# Carte_Servo_Robot_2.net
KiCad netlist of a schematic drawn in Altium Designer
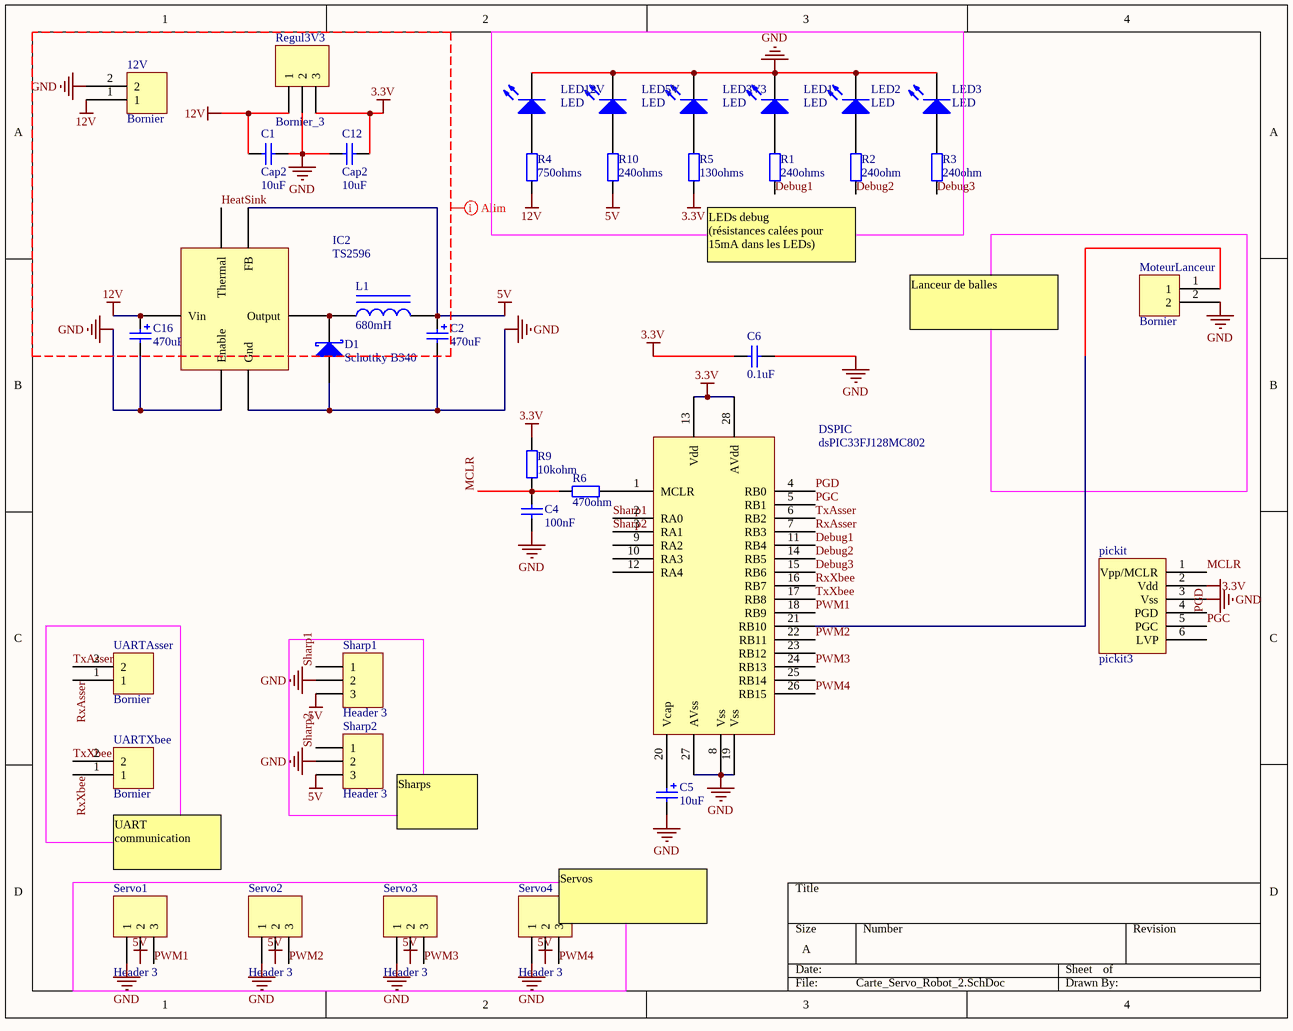
[diagram p0: Carte_Servo_Robot_2.SchDoc]

(export (version "E")
  (design (tool "Eeschema 10.0.6"))
  (components
    (comp (ref "12V")
      (value "Bornier")
      (footprint "Bornier")
      (libsource (lib "lib_Robotronik") (part "Bornier2"))
    )
    (comp (ref "C1")
      (value "Cap2")
      (footprint "CAPA2")
      (description "Capacitor")
      (fields (field (name "ALTIUM_VALUE") "10uF") (field (name "PUBLISHER") "Altium Limited"))
      (libsource (lib "LIBRAIRIE_INTEGREE_PHELMA1") (part "Cap2"))
    )
    (comp (ref "C2")
      (value "470uF")
      (footprint "Capa_pol1")
      (libsource (lib "lib_Robotronik") (part "Capa Pol"))
    )
    (comp (ref "C4")
      (value "100nF")
      (footprint "Capa_plastique")
      (libsource (lib "lib_Robotronik") (part "Capa"))
    )
    (comp (ref "C5")
      (value "10uF")
      (footprint "Capa_pol1")
      (libsource (lib "lib_Robotronik") (part "Capa Pol"))
    )
    (comp (ref "C6")
      (value "0.1uF")
      (footprint "Capa_plastique")
      (libsource (lib "lib_Robotronik") (part "Capa"))
    )
    (comp (ref "C12")
      (value "Cap2")
      (footprint "CAPA2")
      (description "Capacitor")
      (fields (field (name "ALTIUM_VALUE") "10uF") (field (name "PUBLISHER") "Altium Limited"))
      (libsource (lib "LIBRAIRIE_INTEGREE_PHELMA1") (part "Cap2"))
    )
    (comp (ref "C16")
      (value "470uF")
      (footprint "Capa_pol1")
      (libsource (lib "lib_Robotronik") (part "Capa Pol"))
    )
    (comp (ref "D1")
      (value "Schottky B340")
      (footprint "SMC")
      (libsource (lib "lib_Robotronik") (part "Schottky B340"))
    )
    (comp (ref "DSPIC")
      (value "dsPIC33FJ128MC802")
      (footprint "DIP28")
      (libsource (lib "lib_Robotronik") (part "dsPIC33FJ128MC802"))
    )
    (comp (ref "IC2")
      (value "TS2596")
      (footprint "TO263-5L")
      (libsource (lib "lib_Robotronik") (part "TS2596"))
    )
    (comp (ref "L1")
      (value "Inductance")
      (footprint "self")
      (fields (field (name "VALEUR") "680mH"))
      (libsource (lib "lib_Robotronik") (part "Inductance"))
    )
    (comp (ref "LED1") (value "LED") (footprint "Led_5mm") (libsource (lib "lib_Robotronik") (part "LED")))
    (comp (ref "LED2") (value "LED") (footprint "Led_5mm") (libsource (lib "lib_Robotronik") (part "LED")))
    (comp (ref "LED3") (value "LED") (footprint "Led_5mm") (libsource (lib "lib_Robotronik") (part "LED")))
    (comp (ref "LED3V3") (value "LED") (footprint "Led_5mm") (libsource (lib "lib_Robotronik") (part "LED")))
    (comp (ref "LED5V") (value "LED") (footprint "Led_5mm") (libsource (lib "lib_Robotronik") (part "LED")))
    (comp (ref "LED12V") (value "LED") (footprint "Led_5mm") (libsource (lib "lib_Robotronik") (part "LED")))
    (comp (ref "MoteurLanceur")
      (value "Bornier")
      (footprint "Bornier")
      (libsource (lib "") (part "Bornier2_1"))
    )
    (comp (ref "pickit")
      (value "pickit3")
      (footprint "pickit3")
      (libsource (lib "lib_Robotronik") (part "pickit3"))
    )
    (comp (ref "R1")
      (value "240ohms")
      (footprint "traversant 1/4W")
      (libsource (lib "lib_Robotronik") (part "Resistance"))
    )
    (comp (ref "R2")
      (value "240ohm")
      (footprint "traversant 1/4W")
      (libsource (lib "lib_Robotronik") (part "Resistance"))
    )
    (comp (ref "R3")
      (value "240ohm")
      (footprint "traversant 1/4W")
      (libsource (lib "lib_Robotronik") (part "Resistance"))
    )
    (comp (ref "R4")
      (value "750ohms")
      (footprint "traversant 1/4W")
      (libsource (lib "lib_Robotronik") (part "Resistance"))
    )
    (comp (ref "R5")
      (value "130ohms")
      (footprint "traversant 1/4W")
      (libsource (lib "lib_Robotronik") (part "Resistance"))
    )
    (comp (ref "R6")
      (value "470ohm")
      (footprint "traversant 1/4W")
      (libsource (lib "") (part "Resistance_2"))
    )
    (comp (ref "R9")
      (value "10kohm")
      (footprint "traversant 1/4W")
      (libsource (lib "") (part "Resistance_1"))
    )
    (comp (ref "R10")
      (value "240ohms")
      (footprint "traversant 1/4W")
      (libsource (lib "lib_Robotronik") (part "Resistance"))
    )
    (comp (ref "Regul3V3")
      (value "Bornier_3")
      (footprint "Bornier_3")
      (description "Header, 3-Pin")
      (fields (field (name "PUBLISHER") "Altium Limited"))
      (libsource (lib "INTEGRATED_LIBRARY1_CONNECTEURS") (part "Bornier_3"))
    )
    (comp (ref "Servo1")
      (value "Header 3")
      (footprint "HDR1X3")
      (description "Header, 3-Pin")
      (fields (field (name "PUBLISHER") "Altium Limited"))
      (libsource (lib "Miscellaneous Connectors") (part "Header 3"))
    )
    (comp (ref "Servo2")
      (value "Header 3")
      (footprint "HDR1X3")
      (description "Header, 3-Pin")
      (fields (field (name "PUBLISHER") "Altium Limited"))
      (libsource (lib "Miscellaneous Connectors") (part "Header 3"))
    )
    (comp (ref "Servo3")
      (value "Header 3")
      (footprint "HDR1X3")
      (description "Header, 3-Pin")
      (fields (field (name "PUBLISHER") "Altium Limited"))
      (libsource (lib "Miscellaneous Connectors") (part "Header 3"))
    )
    (comp (ref "Servo4")
      (value "Header 3")
      (footprint "HDR1X3")
      (description "Header, 3-Pin")
      (fields (field (name "PUBLISHER") "Altium Limited"))
      (libsource (lib "Miscellaneous Connectors") (part "Header 3"))
    )
    (comp (ref "Sharp1")
      (value "Header 3")
      (footprint "HDR1X3")
      (description "Header, 3-Pin")
      (fields (field (name "PUBLISHER") "Altium Limited"))
      (libsource (lib "") (part "Header 3_1"))
    )
    (comp (ref "Sharp2")
      (value "Header 3")
      (footprint "HDR1X3")
      (description "Header, 3-Pin")
      (fields (field (name "PUBLISHER") "Altium Limited"))
      (libsource (lib "") (part "Header 3_1"))
    )
    (comp (ref "UARTAsser")
      (value "Bornier")
      (footprint "Bornier")
      (libsource (lib "lib_Robotronik") (part "Bornier2"))
    )
    (comp (ref "UARTXbee")
      (value "Bornier")
      (footprint "Bornier")
      (libsource (lib "lib_Robotronik") (part "Bornier2"))
    )
  )
  (nets
    (net (code "1") (name "/Debug1") (class "Default")
      (node (ref "DSPIC") (pin "11") (pinfunction "RB4_11") (pintype "passive"))
      (node (ref "R1") (pin "1") (pinfunction "1_1") (pintype "passive"))
    )
    (net (code "2") (name "/Debug2") (class "Default")
      (node (ref "DSPIC") (pin "14") (pinfunction "RB5_14") (pintype "passive"))
      (node (ref "R2") (pin "1") (pinfunction "1_1") (pintype "passive"))
    )
    (net (code "3") (name "/Debug3") (class "Default")
      (node (ref "DSPIC") (pin "15") (pinfunction "RB6_15") (pintype "passive"))
      (node (ref "R3") (pin "1") (pinfunction "1_1") (pintype "passive"))
    )
    (net (code "4") (name "/HeatSink") (class "Default")
      (node (ref "IC2") (pin "0") (pinfunction "Thermal_0") (pintype "passive"))
    )
    (net (code "5") (name "/MCLR") (class "Default")
      (node (ref "C4") (pin "2") (pinfunction "2_2") (pintype "passive"))
      (node (ref "R6") (pin "2") (pinfunction "2_2") (pintype "passive"))
      (node (ref "R9") (pin "2") (pinfunction "2_2") (pintype "passive"))
      (node (ref "pickit") (pin "1") (pinfunction "Vpp/MCLR_1") (pintype "passive"))
    )
    (net (code "6") (name "/PGC") (class "Default")
      (node (ref "DSPIC") (pin "5") (pinfunction "RB1_5") (pintype "passive"))
      (node (ref "pickit") (pin "5") (pinfunction "PGC_5") (pintype "passive"))
    )
    (net (code "7") (name "/PGD") (class "Default")
      (node (ref "DSPIC") (pin "4") (pinfunction "RB0_4") (pintype "passive"))
      (node (ref "pickit") (pin "4") (pinfunction "PGD_4") (pintype "passive"))
    )
    (net (code "8") (name "/PWM1") (class "Default")
      (node (ref "DSPIC") (pin "18") (pinfunction "RB9_18") (pintype "passive"))
      (node (ref "Servo1") (pin "3") (pinfunction "3_3") (pintype "passive"))
    )
    (net (code "9") (name "/PWM2") (class "Default")
      (node (ref "DSPIC") (pin "22") (pinfunction "RB11_22") (pintype "passive"))
      (node (ref "Servo2") (pin "3") (pinfunction "3_3") (pintype "passive"))
    )
    (net (code "10") (name "/PWM3") (class "Default")
      (node (ref "DSPIC") (pin "24") (pinfunction "RB13_24") (pintype "passive"))
      (node (ref "Servo3") (pin "3") (pinfunction "3_3") (pintype "passive"))
    )
    (net (code "11") (name "/PWM4") (class "Default")
      (node (ref "DSPIC") (pin "26") (pinfunction "RB15_26") (pintype "passive"))
      (node (ref "Servo4") (pin "3") (pinfunction "3_3") (pintype "passive"))
    )
    (net (code "12") (name "/RxAsser") (class "Default")
      (node (ref "DSPIC") (pin "7") (pinfunction "RB3_7") (pintype "passive"))
      (node (ref "UARTAsser") (pin "1") (pinfunction "1_1") (pintype "passive"))
    )
    (net (code "13") (name "/RxXbee") (class "Default")
      (node (ref "DSPIC") (pin "16") (pinfunction "RB7_16") (pintype "passive"))
      (node (ref "UARTXbee") (pin "1") (pinfunction "1_1") (pintype "passive"))
    )
    (net (code "14") (name "/Sharp1") (class "Default")
      (node (ref "DSPIC") (pin "2") (pinfunction "RA0_2") (pintype "passive"))
      (node (ref "Sharp1") (pin "1") (pinfunction "1_1") (pintype "passive"))
    )
    (net (code "15") (name "/Sharp2") (class "Default")
      (node (ref "DSPIC") (pin "3") (pinfunction "RA1_3") (pintype "passive"))
      (node (ref "Sharp2") (pin "1") (pinfunction "1_1") (pintype "passive"))
    )
    (net (code "16") (name "/TxAsser") (class "Default")
      (node (ref "DSPIC") (pin "6") (pinfunction "RB2_6") (pintype "passive"))
      (node (ref "UARTAsser") (pin "2") (pinfunction "2_2") (pintype "passive"))
    )
    (net (code "17") (name "/TxXbee") (class "Default")
      (node (ref "DSPIC") (pin "17") (pinfunction "RB8_17") (pintype "passive"))
      (node (ref "UARTXbee") (pin "2") (pinfunction "2_2") (pintype "passive"))
    )
    (net (code "18") (name "3.3V") (class "Default")
      (node (ref "C12") (pin "2") (pinfunction "2_2") (pintype "passive"))
      (node (ref "C6") (pin "1") (pinfunction "1_1") (pintype "passive"))
      (node (ref "DSPIC") (pin "13") (pinfunction "Vdd_13") (pintype "passive"))
      (node (ref "DSPIC") (pin "28") (pinfunction "AVdd_28") (pintype "passive"))
      (node (ref "R5") (pin "1") (pinfunction "1_1") (pintype "passive"))
      (node (ref "R9") (pin "1") (pinfunction "1_1") (pintype "passive"))
      (node (ref "Regul3V3") (pin "3") (pinfunction "3_3") (pintype "passive"))
      (node (ref "pickit") (pin "2") (pinfunction "Vdd_2") (pintype "passive"))
    )
    (net (code "19") (name "5V") (class "Default")
      (node (ref "C2") (pin "1") (pinfunction "1_1") (pintype "passive"))
      (node (ref "IC2") (pin "4") (pinfunction "FB_4") (pintype "passive"))
      (node (ref "L1") (pin "2") (pinfunction "2_2") (pintype "passive"))
      (node (ref "R10") (pin "1") (pinfunction "1_1") (pintype "passive"))
      (node (ref "Servo1") (pin "2") (pinfunction "2_2") (pintype "passive"))
      (node (ref "Servo2") (pin "2") (pinfunction "2_2") (pintype "passive"))
      (node (ref "Servo3") (pin "2") (pinfunction "2_2") (pintype "passive"))
      (node (ref "Servo4") (pin "2") (pinfunction "2_2") (pintype "passive"))
      (node (ref "Sharp1") (pin "3") (pinfunction "3_3") (pintype "passive"))
      (node (ref "Sharp2") (pin "3") (pinfunction "3_3") (pintype "passive"))
    )
    (net (code "20") (name "12V") (class "Default")
      (node (ref "12V") (pin "1") (pinfunction "1_1") (pintype "passive"))
      (node (ref "C1") (pin "1") (pinfunction "1_1") (pintype "passive"))
      (node (ref "C16") (pin "1") (pinfunction "1_1") (pintype "passive"))
      (node (ref "IC2") (pin "1") (pinfunction "Vin_1") (pintype "passive"))
      (node (ref "R4") (pin "1") (pinfunction "1_1") (pintype "passive"))
      (node (ref "Regul3V3") (pin "1") (pinfunction "1_1") (pintype "passive"))
    )
    (net (code "21") (name "GND") (class "Default")
      (node (ref "12V") (pin "2") (pinfunction "2_2") (pintype "passive"))
      (node (ref "C1") (pin "2") (pinfunction "2_2") (pintype "passive"))
      (node (ref "C12") (pin "1") (pinfunction "1_1") (pintype "passive"))
      (node (ref "C16") (pin "2") (pinfunction "2_2") (pintype "passive"))
      (node (ref "C2") (pin "2") (pinfunction "2_2") (pintype "passive"))
      (node (ref "C4") (pin "1") (pinfunction "1_1") (pintype "passive"))
      (node (ref "C5") (pin "2") (pinfunction "2_2") (pintype "passive"))
      (node (ref "C6") (pin "2") (pinfunction "2_2") (pintype "passive"))
      (node (ref "D1") (pin "1") (pinfunction "A_1") (pintype "passive"))
      (node (ref "DSPIC") (pin "19") (pinfunction "Vss_19") (pintype "passive"))
      (node (ref "DSPIC") (pin "27") (pinfunction "AVss_27") (pintype "passive"))
      (node (ref "DSPIC") (pin "8") (pinfunction "Vss_8") (pintype "passive"))
      (node (ref "IC2") (pin "3") (pinfunction "Gnd_3") (pintype "passive"))
      (node (ref "IC2") (pin "5") (pinfunction "Enable_5") (pintype "passive"))
      (node (ref "LED1") (pin "2") (pinfunction "K_2") (pintype "passive"))
      (node (ref "LED12V") (pin "2") (pinfunction "K_2") (pintype "passive"))
      (node (ref "LED2") (pin "2") (pinfunction "K_2") (pintype "passive"))
      (node (ref "LED3") (pin "2") (pinfunction "K_2") (pintype "passive"))
      (node (ref "LED3V3") (pin "2") (pinfunction "K_2") (pintype "passive"))
      (node (ref "LED5V") (pin "2") (pinfunction "K_2") (pintype "passive"))
      (node (ref "MoteurLanceur") (pin "2") (pinfunction "2_2") (pintype "passive"))
      (node (ref "Regul3V3") (pin "2") (pinfunction "2_2") (pintype "passive"))
      (node (ref "Servo1") (pin "1") (pinfunction "1_1") (pintype "passive"))
      (node (ref "Servo2") (pin "1") (pinfunction "1_1") (pintype "passive"))
      (node (ref "Servo3") (pin "1") (pinfunction "1_1") (pintype "passive"))
      (node (ref "Servo4") (pin "1") (pinfunction "1_1") (pintype "passive"))
      (node (ref "Sharp1") (pin "2") (pinfunction "2_2") (pintype "passive"))
      (node (ref "Sharp2") (pin "2") (pinfunction "2_2") (pintype "passive"))
      (node (ref "pickit") (pin "3") (pinfunction "Vss_3") (pintype "passive"))
    )
    (net (code "22") (name "Net-(D1-K)") (class "Default")
      (node (ref "D1") (pin "2") (pinfunction "K_2") (pintype "passive"))
      (node (ref "IC2") (pin "2") (pinfunction "Output_2") (pintype "passive"))
      (node (ref "L1") (pin "1") (pinfunction "1_1") (pintype "passive"))
    )
    (net (code "23") (name "Net-(DSPIC-MCLR)") (class "Default")
      (node (ref "DSPIC") (pin "1") (pinfunction "MCLR_1") (pintype "passive"))
      (node (ref "R6") (pin "1") (pinfunction "1_1") (pintype "passive"))
    )
    (net (code "24") (name "Net-(DSPIC-RB10)") (class "Default")
      (node (ref "DSPIC") (pin "21") (pinfunction "RB10_21") (pintype "passive"))
      (node (ref "MoteurLanceur") (pin "1") (pinfunction "1_1") (pintype "passive"))
    )
    (net (code "25") (name "Net-(DSPIC-Vcap)") (class "Default")
      (node (ref "C5") (pin "1") (pinfunction "1_1") (pintype "passive"))
      (node (ref "DSPIC") (pin "20") (pinfunction "Vcap_20") (pintype "passive"))
    )
    (net (code "26") (name "Net-(LED1-A)") (class "Default")
      (node (ref "LED1") (pin "1") (pinfunction "A_1") (pintype "passive"))
      (node (ref "R1") (pin "2") (pinfunction "2_2") (pintype "passive"))
    )
    (net (code "27") (name "Net-(LED2-A)") (class "Default")
      (node (ref "LED2") (pin "1") (pinfunction "A_1") (pintype "passive"))
      (node (ref "R2") (pin "2") (pinfunction "2_2") (pintype "passive"))
    )
    (net (code "28") (name "Net-(LED3-A)") (class "Default")
      (node (ref "LED3") (pin "1") (pinfunction "A_1") (pintype "passive"))
      (node (ref "R3") (pin "2") (pinfunction "2_2") (pintype "passive"))
    )
    (net (code "29") (name "Net-(LED3V3-A)") (class "Default")
      (node (ref "LED3V3") (pin "1") (pinfunction "A_1") (pintype "passive"))
      (node (ref "R5") (pin "2") (pinfunction "2_2") (pintype "passive"))
    )
    (net (code "30") (name "Net-(LED5V-A)") (class "Default")
      (node (ref "LED5V") (pin "1") (pinfunction "A_1") (pintype "passive"))
      (node (ref "R10") (pin "2") (pinfunction "2_2") (pintype "passive"))
    )
    (net (code "31") (name "Net-(LED12V-A)") (class "Default")
      (node (ref "LED12V") (pin "1") (pinfunction "A_1") (pintype "passive"))
      (node (ref "R4") (pin "2") (pinfunction "2_2") (pintype "passive"))
    )
    (net (code "32") (name "unconnected-(DSPIC-RA2-Pad9)") (class "Default")
      (node (ref "DSPIC") (pin "9") (pinfunction "RA2_9") (pintype "passive"))
    )
    (net (code "33") (name "unconnected-(DSPIC-RA3-Pad10)") (class "Default")
      (node (ref "DSPIC") (pin "10") (pinfunction "RA3_10") (pintype "passive"))
    )
    (net (code "34") (name "unconnected-(DSPIC-RA4-Pad12)") (class "Default")
      (node (ref "DSPIC") (pin "12") (pinfunction "RA4_12") (pintype "passive"))
    )
    (net (code "35") (name "unconnected-(DSPIC-RB12-Pad23)") (class "Default")
      (node (ref "DSPIC") (pin "23") (pinfunction "RB12_23") (pintype "passive"))
    )
    (net (code "36") (name "unconnected-(DSPIC-RB14-Pad25)") (class "Default")
      (node (ref "DSPIC") (pin "25") (pinfunction "RB14_25") (pintype "passive"))
    )
    (net (code "37") (name "unconnected-(pickit-LVP-Pad6)") (class "Default")
      (node (ref "pickit") (pin "6") (pinfunction "LVP_6") (pintype "passive"))
    )
  )
)
